# EMU.net
KiCad netlist of a schematic drawn in Altium Designer
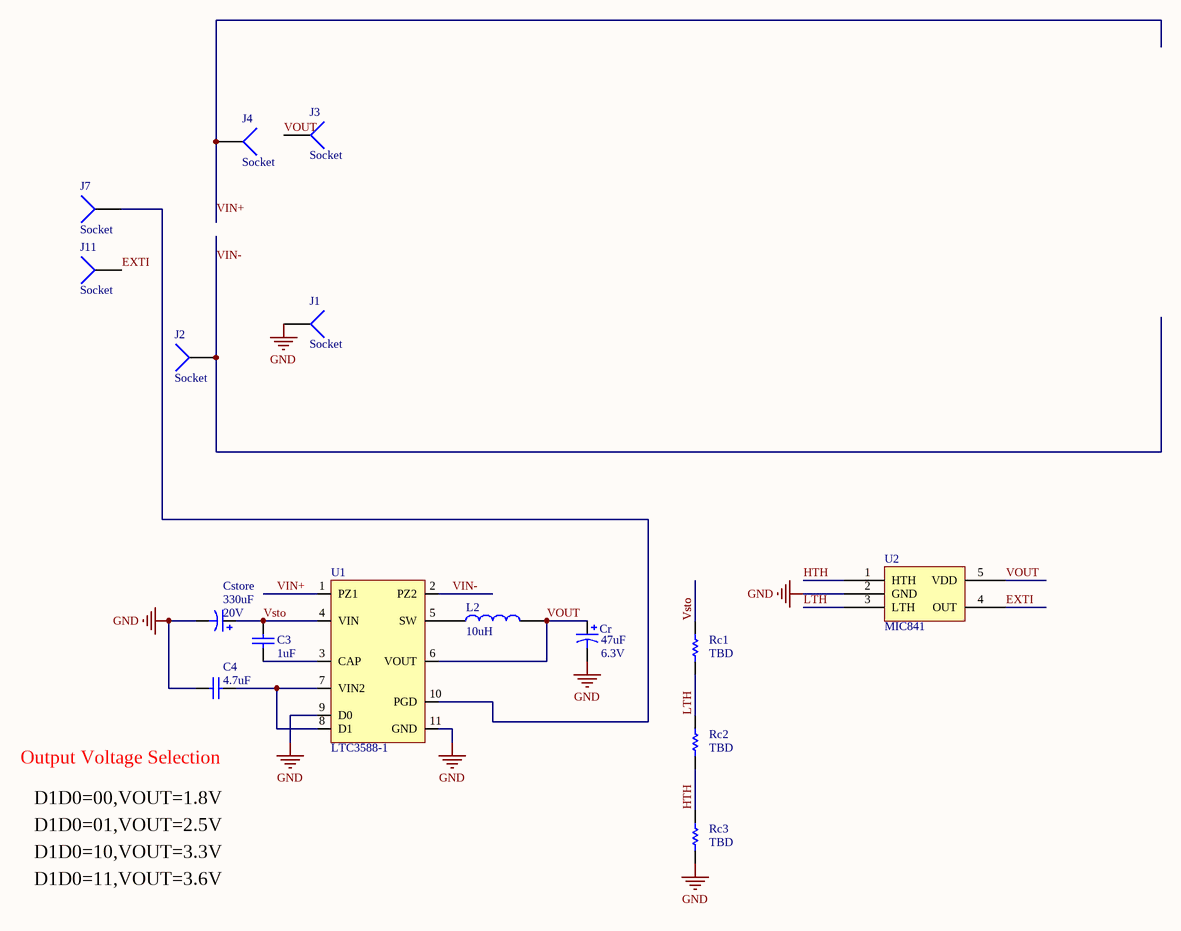
[diagram p0: EMU.SchDoc]

(export (version "E")
  (design (tool "Eeschema 10.0.6"))
  (components
    (comp (ref "C3")
      (value "1uF")
      (footprint "6-0805_N")
      (description "Capacitor")
      (fields (field (name "Comment") "CAP") (field (name "PUBLISHER") "Altium Limited"))
      (libsource (lib "Harry_PCBLib") (part "Cap"))
    )
    (comp (ref "C4")
      (value "4.7uF")
      (footprint "6-0805_N")
      (description "Capacitor")
      (fields (field (name "Comment") "CAP") (field (name "PUBLISHER") "Altium Limited"))
      (libsource (lib "Harry_PCBLib") (part "Cap"))
    )
    (comp (ref "Cr")
      (value "6.3V")
      (footprint "3216[1206]")
      (description "Polarized Capacitor (Radial)")
      (fields (field (name "ALTIUM_VALUE") "47uF") (field (name "PUBLISHER") "Altium Limited"))
      (libsource (lib "Miscellaneous Devices") (part "Cap Pol1"))
    )
    (comp (ref "Cstore")
      (value "330uF")
      (footprint "HDR1X2")
      (description "Polarized Capacitor (Radial)")
      (fields
        (field (name "NOMINAL VOLTAGE") "20V")
        (field (name "Comment") "Cap Pol1")
        (field (name "PUBLISHER") "Altium Limited")
      )
      (libsource (lib "Miscellaneous Devices") (part "Cap Pol1"))
    )
    (comp (ref "J1")
      (value "Socket")
      (footprint "PIN1")
      (fields (field (name "PUBLISHER") "Altium Limited"))
      (libsource (lib "Miscellaneous Connectors") (part "Socket"))
    )
    (comp (ref "J2")
      (value "Socket")
      (footprint "PIN1")
      (fields (field (name "PUBLISHER") "Altium Limited"))
      (libsource (lib "Miscellaneous Connectors") (part "Socket"))
    )
    (comp (ref "J3")
      (value "Socket")
      (footprint "PIN1")
      (fields (field (name "PUBLISHER") "Altium Limited"))
      (libsource (lib "Miscellaneous Connectors") (part "Socket"))
    )
    (comp (ref "J4")
      (value "Socket")
      (footprint "PIN1")
      (fields (field (name "PUBLISHER") "Altium Limited"))
      (libsource (lib "Miscellaneous Connectors") (part "Socket"))
    )
    (comp (ref "J7")
      (value "Socket")
      (footprint "PIN1")
      (fields (field (name "PUBLISHER") "Altium Limited"))
      (libsource (lib "Miscellaneous Connectors") (part "Socket"))
    )
    (comp (ref "J11")
      (value "Socket")
      (footprint "PIN1")
      (fields (field (name "PUBLISHER") "Altium Limited"))
      (libsource (lib "Miscellaneous Connectors") (part "Socket"))
    )
    (comp (ref "L2") (value "10uH") (footprint "SMD SS16") (libsource (lib "Harry_PCBLib") (part "INDUCTOR")))
    (comp (ref "Rc1")
      (value "TBD")
      (footprint "6-0805_N")
      (description "Resistor")
      (fields (field (name "Comment") "Res1") (field (name "PUBLISHER") "Altium Limited"))
      (libsource (lib "Miscellaneous Devices") (part "Res1"))
    )
    (comp (ref "Rc2")
      (value "TBD")
      (footprint "6-0805_N")
      (description "Resistor")
      (fields (field (name "Comment") "Res1") (field (name "PUBLISHER") "Altium Limited"))
      (libsource (lib "Miscellaneous Devices") (part "Res1"))
    )
    (comp (ref "Rc3")
      (value "TBD")
      (footprint "6-0805_N")
      (description "Resistor")
      (fields (field (name "Comment") "Res1") (field (name "PUBLISHER") "Altium Limited"))
      (libsource (lib "Miscellaneous Devices") (part "Res1"))
    )
    (comp (ref "U1")
      (value "LTC3588-1")
      (footprint "LTC 3588-1")
      (description "Nanopower energy harvesting power supply")
      (libsource (lib "Self-power SSHI") (part "LTC3588-1"))
    )
    (comp (ref "U2")
      (value "MIC841")
      (footprint "SOT65P210X90-5L20N")
      (libsource (lib "MIC841") (part "Component_1"))
    )
  )
  (nets
    (net (code "1") (name "/EXTI") (class "Default")
      (node (ref "J11") (pin "1") (pinfunction "1_1") (pintype "passive"))
      (node (ref "U2") (pin "4") (pinfunction "OUT_4") (pintype "passive"))
    )
    (net (code "2") (name "/HTH") (class "Default")
      (node (ref "Rc2") (pin "1") (pinfunction "1_1") (pintype "passive"))
      (node (ref "Rc3") (pin "2") (pinfunction "2_2") (pintype "passive"))
      (node (ref "U2") (pin "1") (pinfunction "HTH_1") (pintype "passive"))
    )
    (net (code "3") (name "/LTH") (class "Default")
      (node (ref "Rc1") (pin "1") (pinfunction "1_1") (pintype "passive"))
      (node (ref "Rc2") (pin "2") (pinfunction "2_2") (pintype "passive"))
      (node (ref "U2") (pin "3") (pinfunction "LTH_3") (pintype "passive"))
    )
    (net (code "4") (name "/VIN+") (class "Default")
      (node (ref "J4") (pin "1") (pinfunction "1_1") (pintype "passive"))
      (node (ref "U1") (pin "1") (pinfunction "PZ1_1") (pintype "passive"))
    )
    (net (code "5") (name "/VIN-") (class "Default")
      (node (ref "J2") (pin "1") (pinfunction "1_1") (pintype "passive"))
      (node (ref "U1") (pin "2") (pinfunction "PZ2_2") (pintype "passive"))
    )
    (net (code "6") (name "/VOUT") (class "Default")
      (node (ref "Cr") (pin "1") (pinfunction "1_1") (pintype "passive"))
      (node (ref "J3") (pin "1") (pinfunction "1_1") (pintype "passive"))
      (node (ref "L2") (pin "2") (pinfunction "2_2") (pintype "passive"))
      (node (ref "U1") (pin "6") (pinfunction "VOUT_6") (pintype "passive"))
      (node (ref "U2") (pin "5") (pinfunction "VDD_5") (pintype "passive"))
    )
    (net (code "7") (name "/Vsto") (class "Default")
      (node (ref "C3") (pin "2") (pinfunction "2_2") (pintype "passive"))
      (node (ref "Cstore") (pin "1") (pinfunction "1_1") (pintype "passive"))
      (node (ref "Rc1") (pin "2") (pinfunction "2_2") (pintype "passive"))
      (node (ref "U1") (pin "4") (pinfunction "VIN_4") (pintype "passive"))
    )
    (net (code "8") (name "GND") (class "Default")
      (node (ref "C4") (pin "2") (pinfunction "2_2") (pintype "passive"))
      (node (ref "Cr") (pin "2") (pinfunction "2_2") (pintype "passive"))
      (node (ref "Cstore") (pin "2") (pinfunction "2_2") (pintype "passive"))
      (node (ref "J1") (pin "1") (pinfunction "1_1") (pintype "passive"))
      (node (ref "Rc3") (pin "1") (pinfunction "1_1") (pintype "passive"))
      (node (ref "U1") (pin "11") (pinfunction "GND_11") (pintype "passive"))
      (node (ref "U1") (pin "9") (pinfunction "D0_9") (pintype "passive"))
      (node (ref "U2") (pin "2") (pinfunction "GND_2") (pintype "passive"))
    )
    (net (code "9") (name "Net-(U1-CAP)") (class "Default")
      (node (ref "C3") (pin "1") (pinfunction "1_1") (pintype "passive"))
      (node (ref "U1") (pin "3") (pinfunction "CAP_3") (pintype "passive"))
    )
    (net (code "10") (name "Net-(U1-D1)") (class "Default")
      (node (ref "C4") (pin "1") (pinfunction "1_1") (pintype "passive"))
      (node (ref "U1") (pin "7") (pinfunction "VIN2_7") (pintype "passive"))
      (node (ref "U1") (pin "8") (pinfunction "D1_8") (pintype "passive"))
    )
    (net (code "11") (name "Net-(U1-PGD)") (class "Default")
      (node (ref "J7") (pin "1") (pinfunction "1_1") (pintype "passive"))
      (node (ref "U1") (pin "10") (pinfunction "PGD_10") (pintype "passive"))
    )
    (net (code "12") (name "Net-(U1-SW)") (class "Default")
      (node (ref "L2") (pin "1") (pinfunction "1_1") (pintype "passive"))
      (node (ref "U1") (pin "5") (pinfunction "SW_5") (pintype "passive"))
    )
  )
)
